# PCB_MULTI_PUMP.net
KiCad netlist of a schematic drawn in EAGLE
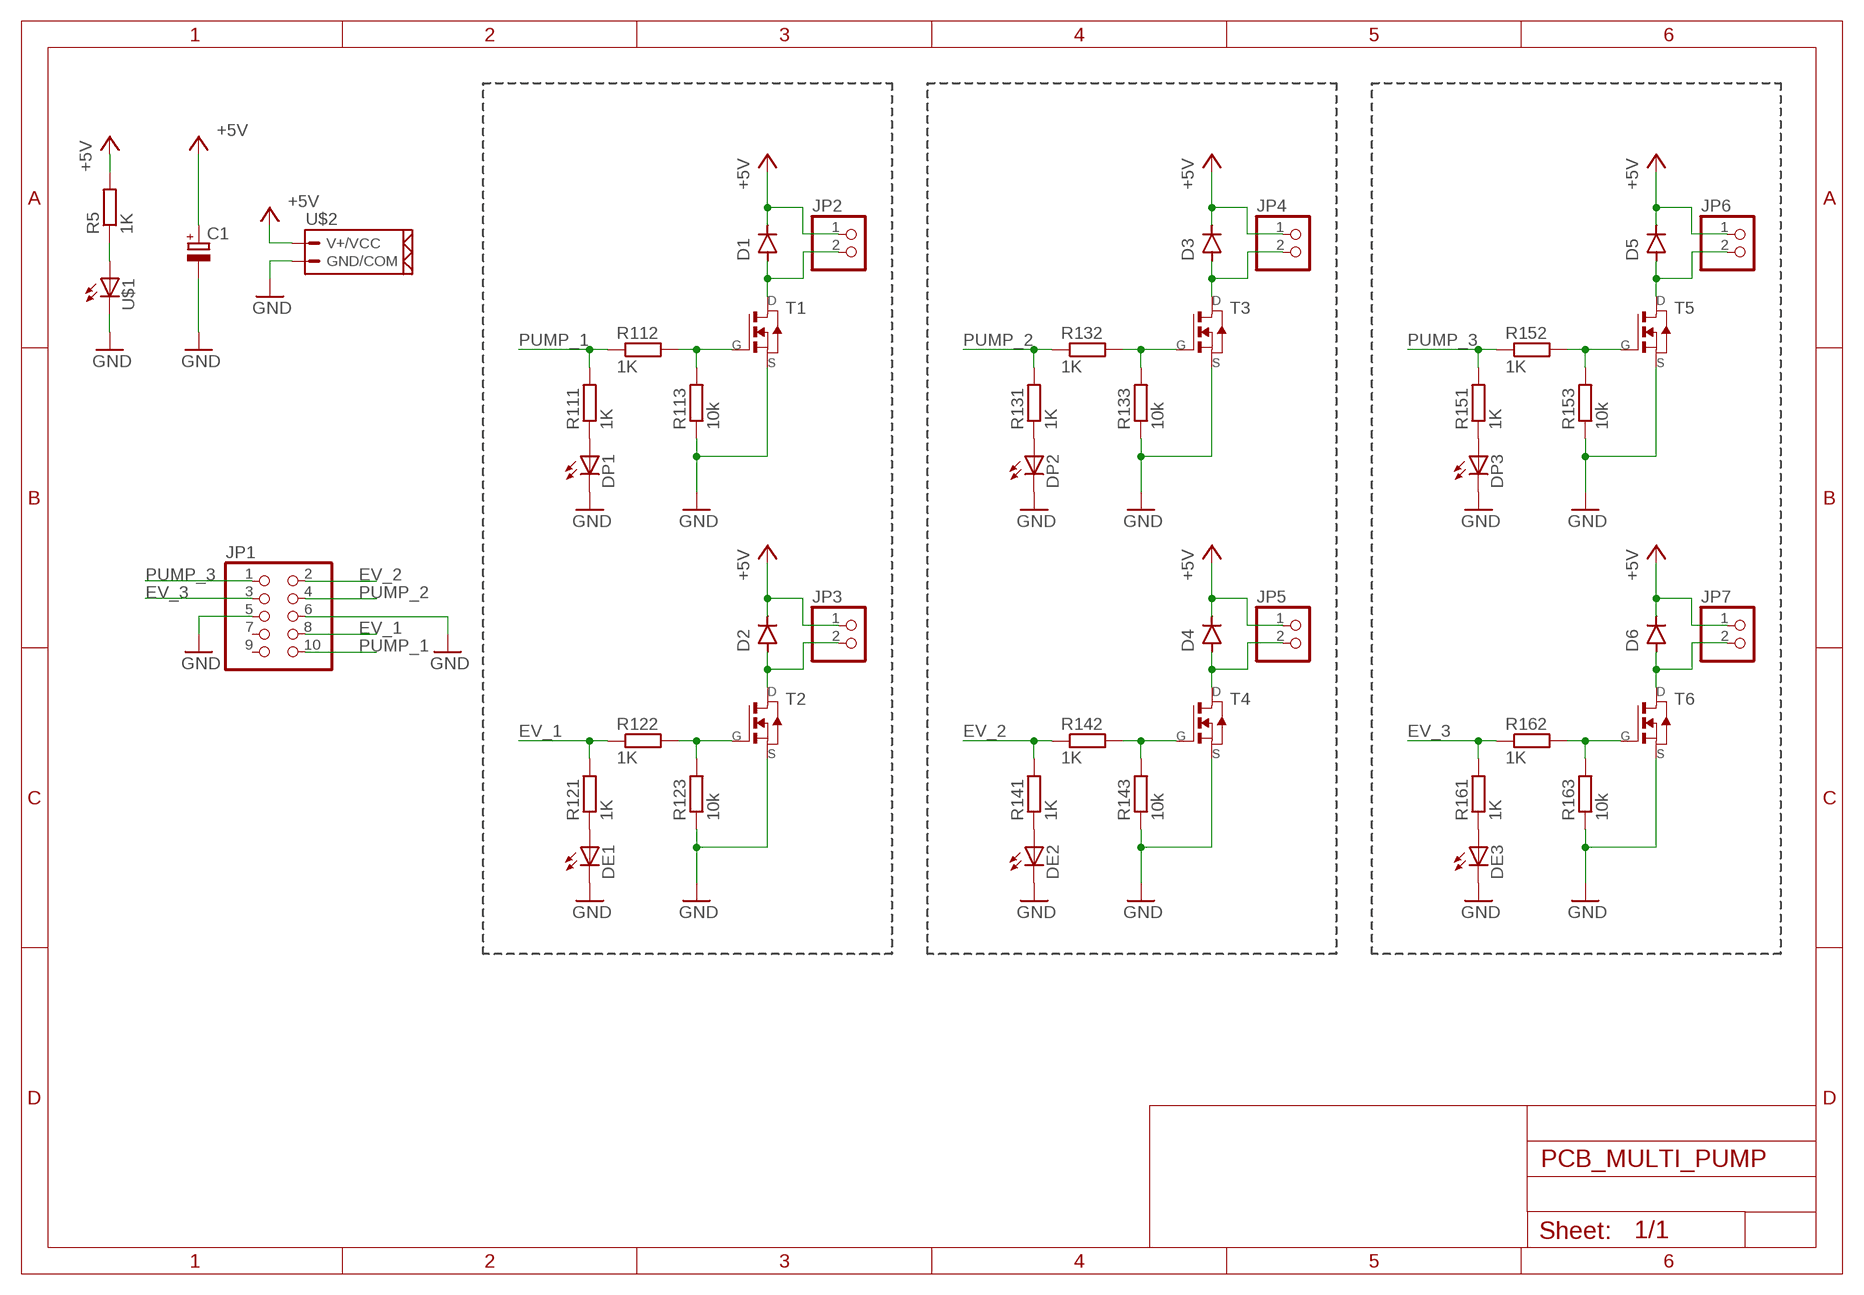
[diagram p0: schematic, sheet 1]

(export (version "E")
  (design (tool "Eeschema 10.0.6"))
  (components
    (comp (ref "C1")
      (value "CPOL-EUE5-10.5")
      (footprint "eagle-import:E5-10,5")
      (libsource (lib "eagle-import") (part "CPOL-EUE5-10.5"))
    )
    (comp (ref "D1")
      (value "GF1")
      (footprint "eagle-import:SMA-DO214AC")
      (libsource (lib "eagle-import") (part "GF1"))
    )
    (comp (ref "D2")
      (value "GF1")
      (footprint "eagle-import:SMA-DO214AC")
      (libsource (lib "eagle-import") (part "GF1"))
    )
    (comp (ref "D3")
      (value "GF1")
      (footprint "eagle-import:SMA-DO214AC")
      (libsource (lib "eagle-import") (part "GF1"))
    )
    (comp (ref "D4")
      (value "GF1")
      (footprint "eagle-import:SMA-DO214AC")
      (libsource (lib "eagle-import") (part "GF1"))
    )
    (comp (ref "D5")
      (value "GF1")
      (footprint "eagle-import:SMA-DO214AC")
      (libsource (lib "eagle-import") (part "GF1"))
    )
    (comp (ref "D6")
      (value "GF1")
      (footprint "eagle-import:SMA-DO214AC")
      (libsource (lib "eagle-import") (part "GF1"))
    )
    (comp (ref "DE1")
      (value "LEDFAB1206")
      (footprint "eagle-import:LED1206FAB")
      (libsource (lib "eagle-import") (part "LEDFAB1206"))
    )
    (comp (ref "DE2")
      (value "LEDFAB1206")
      (footprint "eagle-import:LED1206FAB")
      (libsource (lib "eagle-import") (part "LEDFAB1206"))
    )
    (comp (ref "DE3")
      (value "LEDFAB1206")
      (footprint "eagle-import:LED1206FAB")
      (libsource (lib "eagle-import") (part "LEDFAB1206"))
    )
    (comp (ref "DP1")
      (value "LEDFAB1206")
      (footprint "eagle-import:LED1206FAB")
      (libsource (lib "eagle-import") (part "LEDFAB1206"))
    )
    (comp (ref "DP2")
      (value "LEDFAB1206")
      (footprint "eagle-import:LED1206FAB")
      (libsource (lib "eagle-import") (part "LEDFAB1206"))
    )
    (comp (ref "DP3")
      (value "LEDFAB1206")
      (footprint "eagle-import:LED1206FAB")
      (libsource (lib "eagle-import") (part "LEDFAB1206"))
    )
    (comp (ref "JP1")
      (value "PINHD-2X05_2.54-SMD")
      (footprint "eagle-import:2X05SMD")
      (libsource (lib "eagle-import") (part "PINHD-2X05_2.54-SMD"))
    )
    (comp (ref "JP2")
      (value "PINHD-1X02_2.54-SMD-90°")
      (footprint "eagle-import:1X02SMD_90")
      (libsource (lib "eagle-import") (part "PINHD-1X02_2.54-SMD-90°"))
    )
    (comp (ref "JP3")
      (value "PINHD-1X02_2.54-SMD-90°")
      (footprint "eagle-import:1X02SMD_90")
      (libsource (lib "eagle-import") (part "PINHD-1X02_2.54-SMD-90°"))
    )
    (comp (ref "JP4")
      (value "PINHD-1X02_2.54-SMD-90°")
      (footprint "eagle-import:1X02SMD_90")
      (libsource (lib "eagle-import") (part "PINHD-1X02_2.54-SMD-90°"))
    )
    (comp (ref "JP5")
      (value "PINHD-1X02_2.54-SMD-90°")
      (footprint "eagle-import:1X02SMD_90")
      (libsource (lib "eagle-import") (part "PINHD-1X02_2.54-SMD-90°"))
    )
    (comp (ref "JP6")
      (value "PINHD-1X02_2.54-SMD-90°")
      (footprint "eagle-import:1X02SMD_90")
      (libsource (lib "eagle-import") (part "PINHD-1X02_2.54-SMD-90°"))
    )
    (comp (ref "JP7")
      (value "PINHD-1X02_2.54-SMD-90°")
      (footprint "eagle-import:1X02SMD_90")
      (libsource (lib "eagle-import") (part "PINHD-1X02_2.54-SMD-90°"))
    )
    (comp (ref "R5")
      (value "1K")
      (footprint "eagle-import:R1206")
      (libsource (lib "eagle-import") (part "R-EU_R1206"))
    )
    (comp (ref "R111")
      (value "1K")
      (footprint "eagle-import:R1206")
      (libsource (lib "eagle-import") (part "R-EU_R1206"))
    )
    (comp (ref "R112")
      (value "1K")
      (footprint "eagle-import:R1206")
      (libsource (lib "eagle-import") (part "R-EU_R1206"))
    )
    (comp (ref "R113")
      (value "10k")
      (footprint "eagle-import:R1206")
      (libsource (lib "eagle-import") (part "R-EU_R1206"))
    )
    (comp (ref "R121")
      (value "1K")
      (footprint "eagle-import:R1206")
      (libsource (lib "eagle-import") (part "R-EU_R1206"))
    )
    (comp (ref "R122")
      (value "1K")
      (footprint "eagle-import:R1206")
      (libsource (lib "eagle-import") (part "R-EU_R1206"))
    )
    (comp (ref "R123")
      (value "10k")
      (footprint "eagle-import:R1206")
      (libsource (lib "eagle-import") (part "R-EU_R1206"))
    )
    (comp (ref "R131")
      (value "1K")
      (footprint "eagle-import:R1206")
      (libsource (lib "eagle-import") (part "R-EU_R1206"))
    )
    (comp (ref "R132")
      (value "1K")
      (footprint "eagle-import:R1206")
      (libsource (lib "eagle-import") (part "R-EU_R1206"))
    )
    (comp (ref "R133")
      (value "10k")
      (footprint "eagle-import:R1206")
      (libsource (lib "eagle-import") (part "R-EU_R1206"))
    )
    (comp (ref "R141")
      (value "1K")
      (footprint "eagle-import:R1206")
      (libsource (lib "eagle-import") (part "R-EU_R1206"))
    )
    (comp (ref "R142")
      (value "1K")
      (footprint "eagle-import:R1206")
      (libsource (lib "eagle-import") (part "R-EU_R1206"))
    )
    (comp (ref "R143")
      (value "10k")
      (footprint "eagle-import:R1206")
      (libsource (lib "eagle-import") (part "R-EU_R1206"))
    )
    (comp (ref "R151")
      (value "1K")
      (footprint "eagle-import:R1206")
      (libsource (lib "eagle-import") (part "R-EU_R1206"))
    )
    (comp (ref "R152")
      (value "1K")
      (footprint "eagle-import:R1206")
      (libsource (lib "eagle-import") (part "R-EU_R1206"))
    )
    (comp (ref "R153")
      (value "10k")
      (footprint "eagle-import:R1206")
      (libsource (lib "eagle-import") (part "R-EU_R1206"))
    )
    (comp (ref "R161")
      (value "1K")
      (footprint "eagle-import:R1206")
      (libsource (lib "eagle-import") (part "R-EU_R1206"))
    )
    (comp (ref "R162")
      (value "1K")
      (footprint "eagle-import:R1206")
      (libsource (lib "eagle-import") (part "R-EU_R1206"))
    )
    (comp (ref "R163")
      (value "10k")
      (footprint "eagle-import:R1206")
      (libsource (lib "eagle-import") (part "R-EU_R1206"))
    )
    (comp (ref "T1")
      (value "NMOSFETSOT23")
      (footprint "eagle-import:SOT-23")
      (libsource (lib "eagle-import") (part "NMOSFETSOT23"))
    )
    (comp (ref "T2")
      (value "NMOSFETSOT23")
      (footprint "eagle-import:SOT-23")
      (libsource (lib "eagle-import") (part "NMOSFETSOT23"))
    )
    (comp (ref "T3")
      (value "NMOSFETSOT23")
      (footprint "eagle-import:SOT-23")
      (libsource (lib "eagle-import") (part "NMOSFETSOT23"))
    )
    (comp (ref "T4")
      (value "NMOSFETSOT23")
      (footprint "eagle-import:SOT-23")
      (libsource (lib "eagle-import") (part "NMOSFETSOT23"))
    )
    (comp (ref "T5")
      (value "NMOSFETSOT23")
      (footprint "eagle-import:SOT-23")
      (libsource (lib "eagle-import") (part "NMOSFETSOT23"))
    )
    (comp (ref "T6")
      (value "NMOSFETSOT23")
      (footprint "eagle-import:SOT-23")
      (libsource (lib "eagle-import") (part "NMOSFETSOT23"))
    )
    (comp (ref "U$1")
      (value "LEDFAB1206")
      (footprint "eagle-import:LED1206FAB")
      (libsource (lib "eagle-import") (part "LEDFAB1206"))
    )
    (comp (ref "U$2")
      (value "CONN_02_PUI")
      (footprint "eagle-import:NSK396-2C")
      (libsource (lib "eagle-import") (part "CONN_02_PUI"))
    )
  )
  (nets
    (net (code "1") (name "+5V") (class "Default")
      (node (ref "C1") (pin "+") (pinfunction "+_+") (pintype "passive"))
      (node (ref "D1") (pin "K") (pinfunction "C_K") (pintype "passive"))
      (node (ref "D2") (pin "K") (pinfunction "C_K") (pintype "passive"))
      (node (ref "D3") (pin "K") (pinfunction "C_K") (pintype "passive"))
      (node (ref "D4") (pin "K") (pinfunction "C_K") (pintype "passive"))
      (node (ref "D5") (pin "K") (pinfunction "C_K") (pintype "passive"))
      (node (ref "D6") (pin "K") (pinfunction "C_K") (pintype "passive"))
      (node (ref "JP2") (pin "1") (pinfunction "1_1") (pintype "passive"))
      (node (ref "JP3") (pin "1") (pinfunction "1_1") (pintype "passive"))
      (node (ref "JP4") (pin "1") (pinfunction "1_1") (pintype "passive"))
      (node (ref "JP5") (pin "1") (pinfunction "1_1") (pintype "passive"))
      (node (ref "JP6") (pin "1") (pinfunction "1_1") (pintype "passive"))
      (node (ref "JP7") (pin "1") (pinfunction "1_1") (pintype "passive"))
      (node (ref "R5") (pin "2") (pinfunction "2_2") (pintype "passive"))
      (node (ref "U$2") (pin "P$2") (pinfunction "V+/VCC_P$2") (pintype "passive"))
    )
    (net (code "2") (name "/EV_1") (class "Default")
      (node (ref "JP1") (pin "8") (pinfunction "8_8") (pintype "passive"))
      (node (ref "R121") (pin "2") (pinfunction "2_2") (pintype "passive"))
      (node (ref "R122") (pin "1") (pinfunction "1_1") (pintype "passive"))
    )
    (net (code "3") (name "/EV_2") (class "Default")
      (node (ref "JP1") (pin "2") (pinfunction "2_2") (pintype "passive"))
      (node (ref "R141") (pin "2") (pinfunction "2_2") (pintype "passive"))
      (node (ref "R142") (pin "1") (pinfunction "1_1") (pintype "passive"))
    )
    (net (code "4") (name "/EV_3") (class "Default")
      (node (ref "JP1") (pin "3") (pinfunction "3_3") (pintype "passive"))
      (node (ref "R161") (pin "2") (pinfunction "2_2") (pintype "passive"))
      (node (ref "R162") (pin "1") (pinfunction "1_1") (pintype "passive"))
    )
    (net (code "5") (name "/PUMP_1") (class "Default")
      (node (ref "JP1") (pin "10") (pinfunction "10_10") (pintype "passive"))
      (node (ref "R111") (pin "2") (pinfunction "2_2") (pintype "passive"))
      (node (ref "R112") (pin "1") (pinfunction "1_1") (pintype "passive"))
    )
    (net (code "6") (name "/PUMP_2") (class "Default")
      (node (ref "JP1") (pin "4") (pinfunction "4_4") (pintype "passive"))
      (node (ref "R131") (pin "2") (pinfunction "2_2") (pintype "passive"))
      (node (ref "R132") (pin "1") (pinfunction "1_1") (pintype "passive"))
    )
    (net (code "7") (name "/PUMP_3") (class "Default")
      (node (ref "JP1") (pin "1") (pinfunction "1_1") (pintype "passive"))
      (node (ref "R151") (pin "2") (pinfunction "2_2") (pintype "passive"))
      (node (ref "R152") (pin "1") (pinfunction "1_1") (pintype "passive"))
    )
    (net (code "8") (name "GND") (class "Default")
      (node (ref "C1") (pin "-") (pinfunction "-_-") (pintype "passive"))
      (node (ref "DE1") (pin "2") (pinfunction "C_2") (pintype "passive"))
      (node (ref "DE2") (pin "2") (pinfunction "C_2") (pintype "passive"))
      (node (ref "DE3") (pin "2") (pinfunction "C_2") (pintype "passive"))
      (node (ref "DP1") (pin "2") (pinfunction "C_2") (pintype "passive"))
      (node (ref "DP2") (pin "2") (pinfunction "C_2") (pintype "passive"))
      (node (ref "DP3") (pin "2") (pinfunction "C_2") (pintype "passive"))
      (node (ref "JP1") (pin "5") (pinfunction "5_5") (pintype "passive"))
      (node (ref "JP1") (pin "6") (pinfunction "6_6") (pintype "passive"))
      (node (ref "R113") (pin "1") (pinfunction "1_1") (pintype "passive"))
      (node (ref "R123") (pin "1") (pinfunction "1_1") (pintype "passive"))
      (node (ref "R133") (pin "1") (pinfunction "1_1") (pintype "passive"))
      (node (ref "R143") (pin "1") (pinfunction "1_1") (pintype "passive"))
      (node (ref "R153") (pin "1") (pinfunction "1_1") (pintype "passive"))
      (node (ref "R163") (pin "1") (pinfunction "1_1") (pintype "passive"))
      (node (ref "T1") (pin "2") (pinfunction "S_2") (pintype "passive"))
      (node (ref "T2") (pin "2") (pinfunction "S_2") (pintype "passive"))
      (node (ref "T3") (pin "2") (pinfunction "S_2") (pintype "passive"))
      (node (ref "T4") (pin "2") (pinfunction "S_2") (pintype "passive"))
      (node (ref "T5") (pin "2") (pinfunction "S_2") (pintype "passive"))
      (node (ref "T6") (pin "2") (pinfunction "S_2") (pintype "passive"))
      (node (ref "U$1") (pin "2") (pinfunction "C_2") (pintype "passive"))
      (node (ref "U$2") (pin "P$1") (pinfunction "GND/COM_P$1") (pintype "passive"))
    )
    (net (code "9") (name "Net-(DE1-A)") (class "Default")
      (node (ref "DE1") (pin "1") (pinfunction "A_1") (pintype "passive"))
      (node (ref "R121") (pin "1") (pinfunction "1_1") (pintype "passive"))
    )
    (net (code "10") (name "Net-(DE2-A)") (class "Default")
      (node (ref "DE2") (pin "1") (pinfunction "A_1") (pintype "passive"))
      (node (ref "R141") (pin "1") (pinfunction "1_1") (pintype "passive"))
    )
    (net (code "11") (name "Net-(DE3-A)") (class "Default")
      (node (ref "DE3") (pin "1") (pinfunction "A_1") (pintype "passive"))
      (node (ref "R161") (pin "1") (pinfunction "1_1") (pintype "passive"))
    )
    (net (code "12") (name "Net-(DP1-A)") (class "Default")
      (node (ref "DP1") (pin "1") (pinfunction "A_1") (pintype "passive"))
      (node (ref "R111") (pin "1") (pinfunction "1_1") (pintype "passive"))
    )
    (net (code "13") (name "Net-(DP2-A)") (class "Default")
      (node (ref "DP2") (pin "1") (pinfunction "A_1") (pintype "passive"))
      (node (ref "R131") (pin "1") (pinfunction "1_1") (pintype "passive"))
    )
    (net (code "14") (name "Net-(DP3-A)") (class "Default")
      (node (ref "DP3") (pin "1") (pinfunction "A_1") (pintype "passive"))
      (node (ref "R151") (pin "1") (pinfunction "1_1") (pintype "passive"))
    )
    (net (code "15") (name "Net-(T1-D)") (class "Default")
      (node (ref "D1") (pin "A") (pinfunction "A_A") (pintype "passive"))
      (node (ref "JP2") (pin "2") (pinfunction "2_2") (pintype "passive"))
      (node (ref "T1") (pin "1") (pinfunction "D_1") (pintype "passive"))
    )
    (net (code "16") (name "Net-(T1-G)") (class "Default")
      (node (ref "R112") (pin "2") (pinfunction "2_2") (pintype "passive"))
      (node (ref "R113") (pin "2") (pinfunction "2_2") (pintype "passive"))
      (node (ref "T1") (pin "3") (pinfunction "G_3") (pintype "passive"))
    )
    (net (code "17") (name "Net-(T2-D)") (class "Default")
      (node (ref "D2") (pin "A") (pinfunction "A_A") (pintype "passive"))
      (node (ref "JP3") (pin "2") (pinfunction "2_2") (pintype "passive"))
      (node (ref "T2") (pin "1") (pinfunction "D_1") (pintype "passive"))
    )
    (net (code "18") (name "Net-(T2-G)") (class "Default")
      (node (ref "R122") (pin "2") (pinfunction "2_2") (pintype "passive"))
      (node (ref "R123") (pin "2") (pinfunction "2_2") (pintype "passive"))
      (node (ref "T2") (pin "3") (pinfunction "G_3") (pintype "passive"))
    )
    (net (code "19") (name "Net-(T3-D)") (class "Default")
      (node (ref "D3") (pin "A") (pinfunction "A_A") (pintype "passive"))
      (node (ref "JP4") (pin "2") (pinfunction "2_2") (pintype "passive"))
      (node (ref "T3") (pin "1") (pinfunction "D_1") (pintype "passive"))
    )
    (net (code "20") (name "Net-(T3-G)") (class "Default")
      (node (ref "R132") (pin "2") (pinfunction "2_2") (pintype "passive"))
      (node (ref "R133") (pin "2") (pinfunction "2_2") (pintype "passive"))
      (node (ref "T3") (pin "3") (pinfunction "G_3") (pintype "passive"))
    )
    (net (code "21") (name "Net-(T4-D)") (class "Default")
      (node (ref "D4") (pin "A") (pinfunction "A_A") (pintype "passive"))
      (node (ref "JP5") (pin "2") (pinfunction "2_2") (pintype "passive"))
      (node (ref "T4") (pin "1") (pinfunction "D_1") (pintype "passive"))
    )
    (net (code "22") (name "Net-(T4-G)") (class "Default")
      (node (ref "R142") (pin "2") (pinfunction "2_2") (pintype "passive"))
      (node (ref "R143") (pin "2") (pinfunction "2_2") (pintype "passive"))
      (node (ref "T4") (pin "3") (pinfunction "G_3") (pintype "passive"))
    )
    (net (code "23") (name "Net-(T5-D)") (class "Default")
      (node (ref "D5") (pin "A") (pinfunction "A_A") (pintype "passive"))
      (node (ref "JP6") (pin "2") (pinfunction "2_2") (pintype "passive"))
      (node (ref "T5") (pin "1") (pinfunction "D_1") (pintype "passive"))
    )
    (net (code "24") (name "Net-(T5-G)") (class "Default")
      (node (ref "R152") (pin "2") (pinfunction "2_2") (pintype "passive"))
      (node (ref "R153") (pin "2") (pinfunction "2_2") (pintype "passive"))
      (node (ref "T5") (pin "3") (pinfunction "G_3") (pintype "passive"))
    )
    (net (code "25") (name "Net-(T6-D)") (class "Default")
      (node (ref "D6") (pin "A") (pinfunction "A_A") (pintype "passive"))
      (node (ref "JP7") (pin "2") (pinfunction "2_2") (pintype "passive"))
      (node (ref "T6") (pin "1") (pinfunction "D_1") (pintype "passive"))
    )
    (net (code "26") (name "Net-(T6-G)") (class "Default")
      (node (ref "R162") (pin "2") (pinfunction "2_2") (pintype "passive"))
      (node (ref "R163") (pin "2") (pinfunction "2_2") (pintype "passive"))
      (node (ref "T6") (pin "3") (pinfunction "G_3") (pintype "passive"))
    )
    (net (code "27") (name "Net-(U$1-A)") (class "Default")
      (node (ref "R5") (pin "1") (pinfunction "1_1") (pintype "passive"))
      (node (ref "U$1") (pin "1") (pinfunction "A_1") (pintype "passive"))
    )
    (net (code "28") (name "unconnected-(JP1-Pad7)") (class "Default")
      (node (ref "JP1") (pin "7") (pinfunction "7_7") (pintype "passive"))
    )
    (net (code "29") (name "unconnected-(JP1-Pad9)") (class "Default")
      (node (ref "JP1") (pin "9") (pinfunction "9_9") (pintype "passive"))
    )
  )
)
